# LED_2.net
KiCad netlist of a schematic drawn in EAGLE
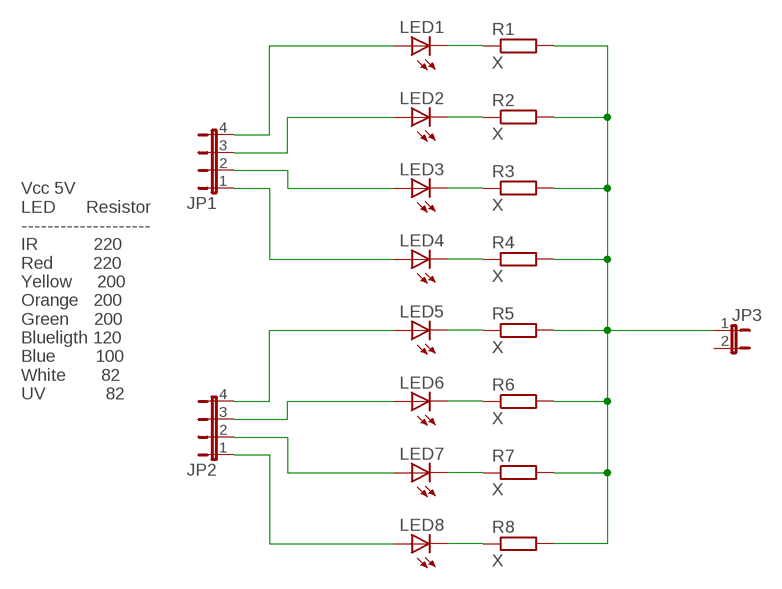
[diagram p0: schematic, sheet 1]

(export (version "E")
  (design (tool "Eeschema 10.0.6"))
  (components
    (comp (ref "JP1")
      (value "JP4E")
      (footprint "eagle-import:JP4")
      (libsource (lib "eagle-import") (part "JP4E"))
    )
    (comp (ref "JP2")
      (value "JP4E")
      (footprint "eagle-import:JP4")
      (libsource (lib "eagle-import") (part "JP4E"))
    )
    (comp (ref "JP3")
      (value "JP1E")
      (footprint "eagle-import:JP1")
      (libsource (lib "eagle-import") (part "JP1E"))
    )
    (comp (ref "LED1")
      (value "LED5MM")
      (footprint "eagle-import:LED5MM")
      (libsource (lib "eagle-import") (part "LED5MM"))
    )
    (comp (ref "LED2")
      (value "LED5MM")
      (footprint "eagle-import:LED5MM")
      (libsource (lib "eagle-import") (part "LED5MM"))
    )
    (comp (ref "LED3")
      (value "LED5MM")
      (footprint "eagle-import:LED5MM")
      (libsource (lib "eagle-import") (part "LED5MM"))
    )
    (comp (ref "LED4")
      (value "LED5MM")
      (footprint "eagle-import:LED5MM")
      (libsource (lib "eagle-import") (part "LED5MM"))
    )
    (comp (ref "LED5")
      (value "LED5MM")
      (footprint "eagle-import:LED5MM")
      (libsource (lib "eagle-import") (part "LED5MM"))
    )
    (comp (ref "LED6")
      (value "LED5MM")
      (footprint "eagle-import:LED5MM")
      (libsource (lib "eagle-import") (part "LED5MM"))
    )
    (comp (ref "LED7")
      (value "LED5MM")
      (footprint "eagle-import:LED5MM")
      (libsource (lib "eagle-import") (part "LED5MM"))
    )
    (comp (ref "LED8")
      (value "LED5MM")
      (footprint "eagle-import:LED5MM")
      (libsource (lib "eagle-import") (part "LED5MM"))
    )
    (comp (ref "R1")
      (value "X")
      (footprint "eagle-import:0411V")
      (libsource (lib "eagle-import") (part "R-EU_0411/3V"))
    )
    (comp (ref "R2")
      (value "X")
      (footprint "eagle-import:0411V")
      (libsource (lib "eagle-import") (part "R-EU_0411/3V"))
    )
    (comp (ref "R3")
      (value "X")
      (footprint "eagle-import:0411V")
      (libsource (lib "eagle-import") (part "R-EU_0411/3V"))
    )
    (comp (ref "R4")
      (value "X")
      (footprint "eagle-import:0411V")
      (libsource (lib "eagle-import") (part "R-EU_0411/3V"))
    )
    (comp (ref "R5")
      (value "X")
      (footprint "eagle-import:0411V")
      (libsource (lib "eagle-import") (part "R-EU_0411/3V"))
    )
    (comp (ref "R6")
      (value "X")
      (footprint "eagle-import:0411V")
      (libsource (lib "eagle-import") (part "R-EU_0411/3V"))
    )
    (comp (ref "R7")
      (value "X")
      (footprint "eagle-import:0411V")
      (libsource (lib "eagle-import") (part "R-EU_0411/3V"))
    )
    (comp (ref "R8")
      (value "X")
      (footprint "eagle-import:0411V")
      (libsource (lib "eagle-import") (part "R-EU_0411/3V"))
    )
  )
  (nets
    (net (code "1") (name "Net-(JP1-Pad1)") (class "Default")
      (node (ref "JP1") (pin "1") (pinfunction "1_1") (pintype "passive"))
      (node (ref "LED4") (pin "A") (pinfunction "A_A") (pintype "passive"))
    )
    (net (code "2") (name "Net-(JP1-Pad2)") (class "Default")
      (node (ref "JP1") (pin "2") (pinfunction "2_2") (pintype "passive"))
      (node (ref "LED3") (pin "A") (pinfunction "A_A") (pintype "passive"))
    )
    (net (code "3") (name "Net-(JP1-Pad3)") (class "Default")
      (node (ref "JP1") (pin "3") (pinfunction "3_3") (pintype "passive"))
      (node (ref "LED2") (pin "A") (pinfunction "A_A") (pintype "passive"))
    )
    (net (code "4") (name "Net-(JP1-Pad4)") (class "Default")
      (node (ref "JP1") (pin "4") (pinfunction "4_4") (pintype "passive"))
      (node (ref "LED1") (pin "A") (pinfunction "A_A") (pintype "passive"))
    )
    (net (code "5") (name "Net-(JP2-Pad1)") (class "Default")
      (node (ref "JP2") (pin "1") (pinfunction "1_1") (pintype "passive"))
      (node (ref "LED8") (pin "A") (pinfunction "A_A") (pintype "passive"))
    )
    (net (code "6") (name "Net-(JP2-Pad2)") (class "Default")
      (node (ref "JP2") (pin "2") (pinfunction "2_2") (pintype "passive"))
      (node (ref "LED7") (pin "A") (pinfunction "A_A") (pintype "passive"))
    )
    (net (code "7") (name "Net-(JP2-Pad3)") (class "Default")
      (node (ref "JP2") (pin "3") (pinfunction "3_3") (pintype "passive"))
      (node (ref "LED6") (pin "A") (pinfunction "A_A") (pintype "passive"))
    )
    (net (code "8") (name "Net-(JP2-Pad4)") (class "Default")
      (node (ref "JP2") (pin "4") (pinfunction "4_4") (pintype "passive"))
      (node (ref "LED5") (pin "A") (pinfunction "A_A") (pintype "passive"))
    )
    (net (code "9") (name "Net-(JP3-Pad1)") (class "Default")
      (node (ref "JP3") (pin "1") (pinfunction "1_1") (pintype "passive"))
      (node (ref "R1") (pin "2") (pinfunction "2_2") (pintype "passive"))
      (node (ref "R2") (pin "2") (pinfunction "2_2") (pintype "passive"))
      (node (ref "R3") (pin "2") (pinfunction "2_2") (pintype "passive"))
      (node (ref "R4") (pin "2") (pinfunction "2_2") (pintype "passive"))
      (node (ref "R5") (pin "2") (pinfunction "2_2") (pintype "passive"))
      (node (ref "R6") (pin "2") (pinfunction "2_2") (pintype "passive"))
      (node (ref "R7") (pin "2") (pinfunction "2_2") (pintype "passive"))
      (node (ref "R8") (pin "2") (pinfunction "2_2") (pintype "passive"))
    )
    (net (code "10") (name "Net-(LED1-C)") (class "Default")
      (node (ref "LED1") (pin "K") (pinfunction "C_K") (pintype "passive"))
      (node (ref "R1") (pin "1") (pinfunction "1_1") (pintype "passive"))
    )
    (net (code "11") (name "Net-(LED2-C)") (class "Default")
      (node (ref "LED2") (pin "K") (pinfunction "C_K") (pintype "passive"))
      (node (ref "R2") (pin "1") (pinfunction "1_1") (pintype "passive"))
    )
    (net (code "12") (name "Net-(LED3-C)") (class "Default")
      (node (ref "LED3") (pin "K") (pinfunction "C_K") (pintype "passive"))
      (node (ref "R3") (pin "1") (pinfunction "1_1") (pintype "passive"))
    )
    (net (code "13") (name "Net-(LED4-C)") (class "Default")
      (node (ref "LED4") (pin "K") (pinfunction "C_K") (pintype "passive"))
      (node (ref "R4") (pin "1") (pinfunction "1_1") (pintype "passive"))
    )
    (net (code "14") (name "Net-(LED5-C)") (class "Default")
      (node (ref "LED5") (pin "K") (pinfunction "C_K") (pintype "passive"))
      (node (ref "R5") (pin "1") (pinfunction "1_1") (pintype "passive"))
    )
    (net (code "15") (name "Net-(LED6-C)") (class "Default")
      (node (ref "LED6") (pin "K") (pinfunction "C_K") (pintype "passive"))
      (node (ref "R6") (pin "1") (pinfunction "1_1") (pintype "passive"))
    )
    (net (code "16") (name "Net-(LED7-C)") (class "Default")
      (node (ref "LED7") (pin "K") (pinfunction "C_K") (pintype "passive"))
      (node (ref "R7") (pin "1") (pinfunction "1_1") (pintype "passive"))
    )
    (net (code "17") (name "Net-(LED8-C)") (class "Default")
      (node (ref "LED8") (pin "K") (pinfunction "C_K") (pintype "passive"))
      (node (ref "R8") (pin "1") (pinfunction "1_1") (pintype "passive"))
    )
    (net (code "18") (name "unconnected-(JP3-Pad2)") (class "Default")
      (node (ref "JP3") (pin "2") (pinfunction "2_2") (pintype "passive"))
    )
  )
)
